# 77_TP_interface.net
KiCad netlist of a schematic drawn in Altium Designer
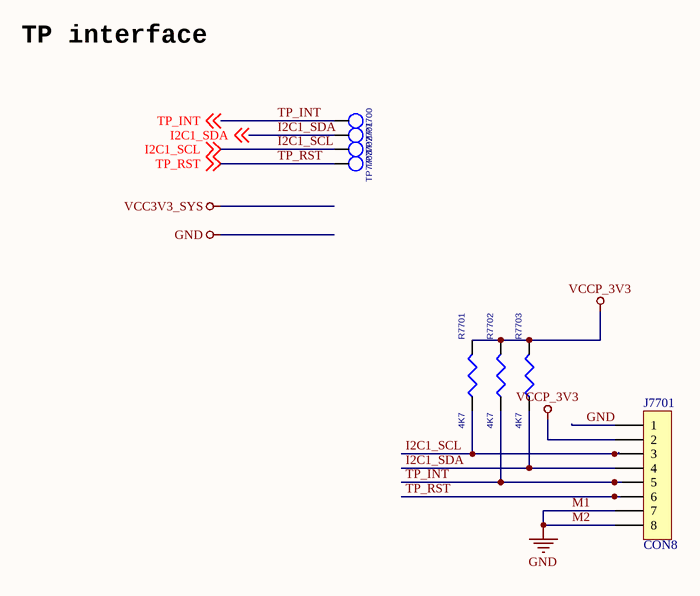
[diagram p0: 77_TP_interface.SchDoc]

(export (version "E")
  (design (tool "Eeschema 10.0.6"))
  (components
    (comp (ref "J7701")
      (value "CON8")
      (footprint "X05A10H06G")
      (description "Connector")
      (libsource (lib "杂元件库") (part "CON8"))
    )
    (comp (ref "R7701")
      (value "4K7")
      (footprint "R0402")
      (description "ROHS CHIP RES 1.65KOhm 1/16W +/-1%")
      (libsource (lib "RK3128(Y2)_2X16BIT_V0_1_20201001") (part "RES 1B"))
    )
    (comp (ref "R7702")
      (value "4K7")
      (footprint "R0402")
      (description "ROHS CHIP RES 1.65KOhm 1/16W +/-1%")
      (libsource (lib "RK3128(Y2)_2X16BIT_V0_1_20201001") (part "RES 1B"))
    )
    (comp (ref "R7703")
      (value "4K7")
      (footprint "R0402")
      (description "ROHS CHIP RES 1.65KOhm 1/16W +/-1%")
      (libsource (lib "RK3128(Y2)_2X16BIT_V0_1_20201001") (part "RES 1B"))
    )
    (comp (ref "TP7700")
      (value "TP_0.7")
      (footprint "TEST")
      (description "Test Point 0.7mm")
      (fields (field (name "CREATED BY") "JJJ"))
      (libsource (lib "*") (part "TP"))
    )
    (comp (ref "TP7701")
      (value "TP_0.7")
      (footprint "TEST")
      (description "Test Point 0.7mm")
      (fields (field (name "CREATED BY") "JJJ"))
      (libsource (lib "*") (part "TP"))
    )
    (comp (ref "TP7702")
      (value "TP_0.7")
      (footprint "TEST")
      (description "Test Point 0.7mm")
      (fields (field (name "CREATED BY") "JJJ"))
      (libsource (lib "*") (part "TP"))
    )
    (comp (ref "TP7703")
      (value "TP_0.7")
      (footprint "TEST")
      (description "Test Point 0.7mm")
      (fields (field (name "CREATED BY") "JJJ"))
      (libsource (lib "*") (part "TP"))
    )
  )
  (nets
    (net (code "1") (name "GND") (class "Default")
      (node (ref "J7701") (pin "1") (pinfunction "1_1") (pintype "passive"))
      (node (ref "J7701") (pin "7") (pinfunction "7_7") (pintype "passive"))
      (node (ref "J7701") (pin "8") (pinfunction "8_8") (pintype "passive"))
    )
    (net (code "2") (name "I2C1_SCL") (class "Default")
      (node (ref "J7701") (pin "3") (pinfunction "3_3") (pintype "passive"))
      (node (ref "R7701") (pin "1") (pinfunction "1_1") (pintype "passive"))
      (node (ref "TP7702") (pin "1") (pinfunction "1_1") (pintype "passive"))
    )
    (net (code "3") (name "I2C1_SDA") (class "Default")
      (node (ref "J7701") (pin "4") (pinfunction "4_4") (pintype "passive"))
      (node (ref "R7703") (pin "1") (pinfunction "1_1") (pintype "passive"))
      (node (ref "TP7701") (pin "1") (pinfunction "1_1") (pintype "passive"))
    )
    (net (code "4") (name "TP_INT") (class "Default")
      (node (ref "J7701") (pin "5") (pinfunction "5_5") (pintype "passive"))
      (node (ref "R7702") (pin "1") (pinfunction "1_1") (pintype "passive"))
      (node (ref "TP7700") (pin "1") (pinfunction "1_1") (pintype "passive"))
    )
    (net (code "5") (name "TP_RST") (class "Default")
      (node (ref "J7701") (pin "6") (pinfunction "6_6") (pintype "passive"))
      (node (ref "TP7703") (pin "1") (pinfunction "1_1") (pintype "passive"))
    )
    (net (code "7") (name "VCCP_3V3") (class "Default")
      (node (ref "J7701") (pin "2") (pinfunction "2_2") (pintype "passive"))
      (node (ref "R7701") (pin "2") (pinfunction "2_2") (pintype "passive"))
      (node (ref "R7702") (pin "2") (pinfunction "2_2") (pintype "passive"))
      (node (ref "R7703") (pin "2") (pinfunction "2_2") (pintype "passive"))
    )
  )
)
